# Intan_Interface.net
KiCad netlist of a schematic drawn in Altium Designer
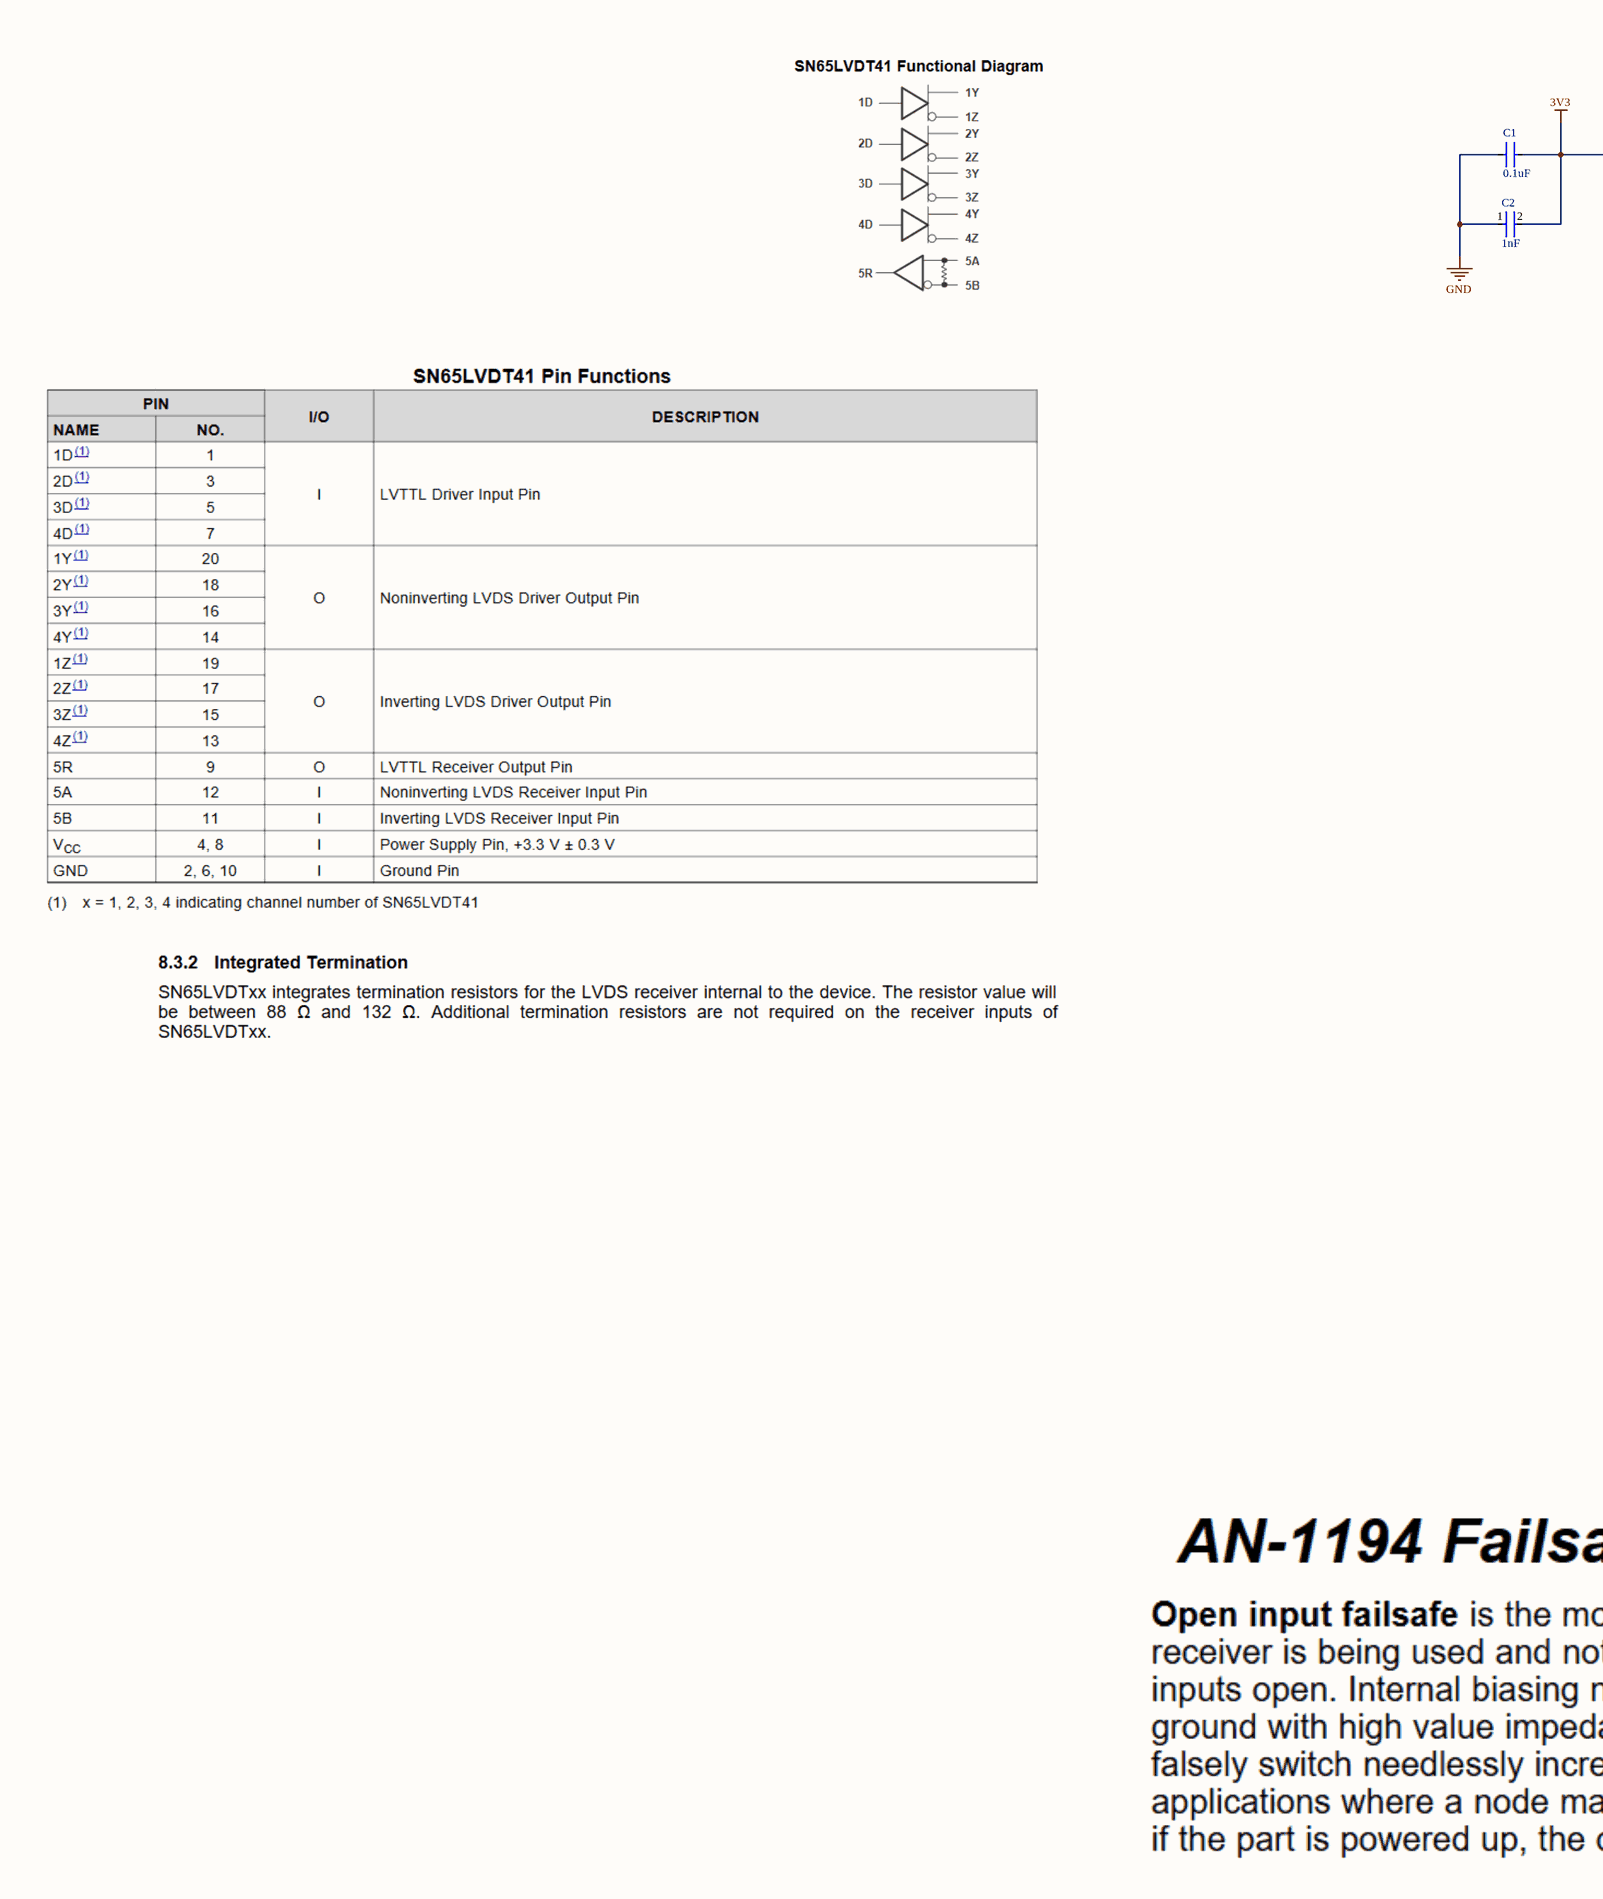
[diagram p0: Intan_Interface.SchDoc, left]
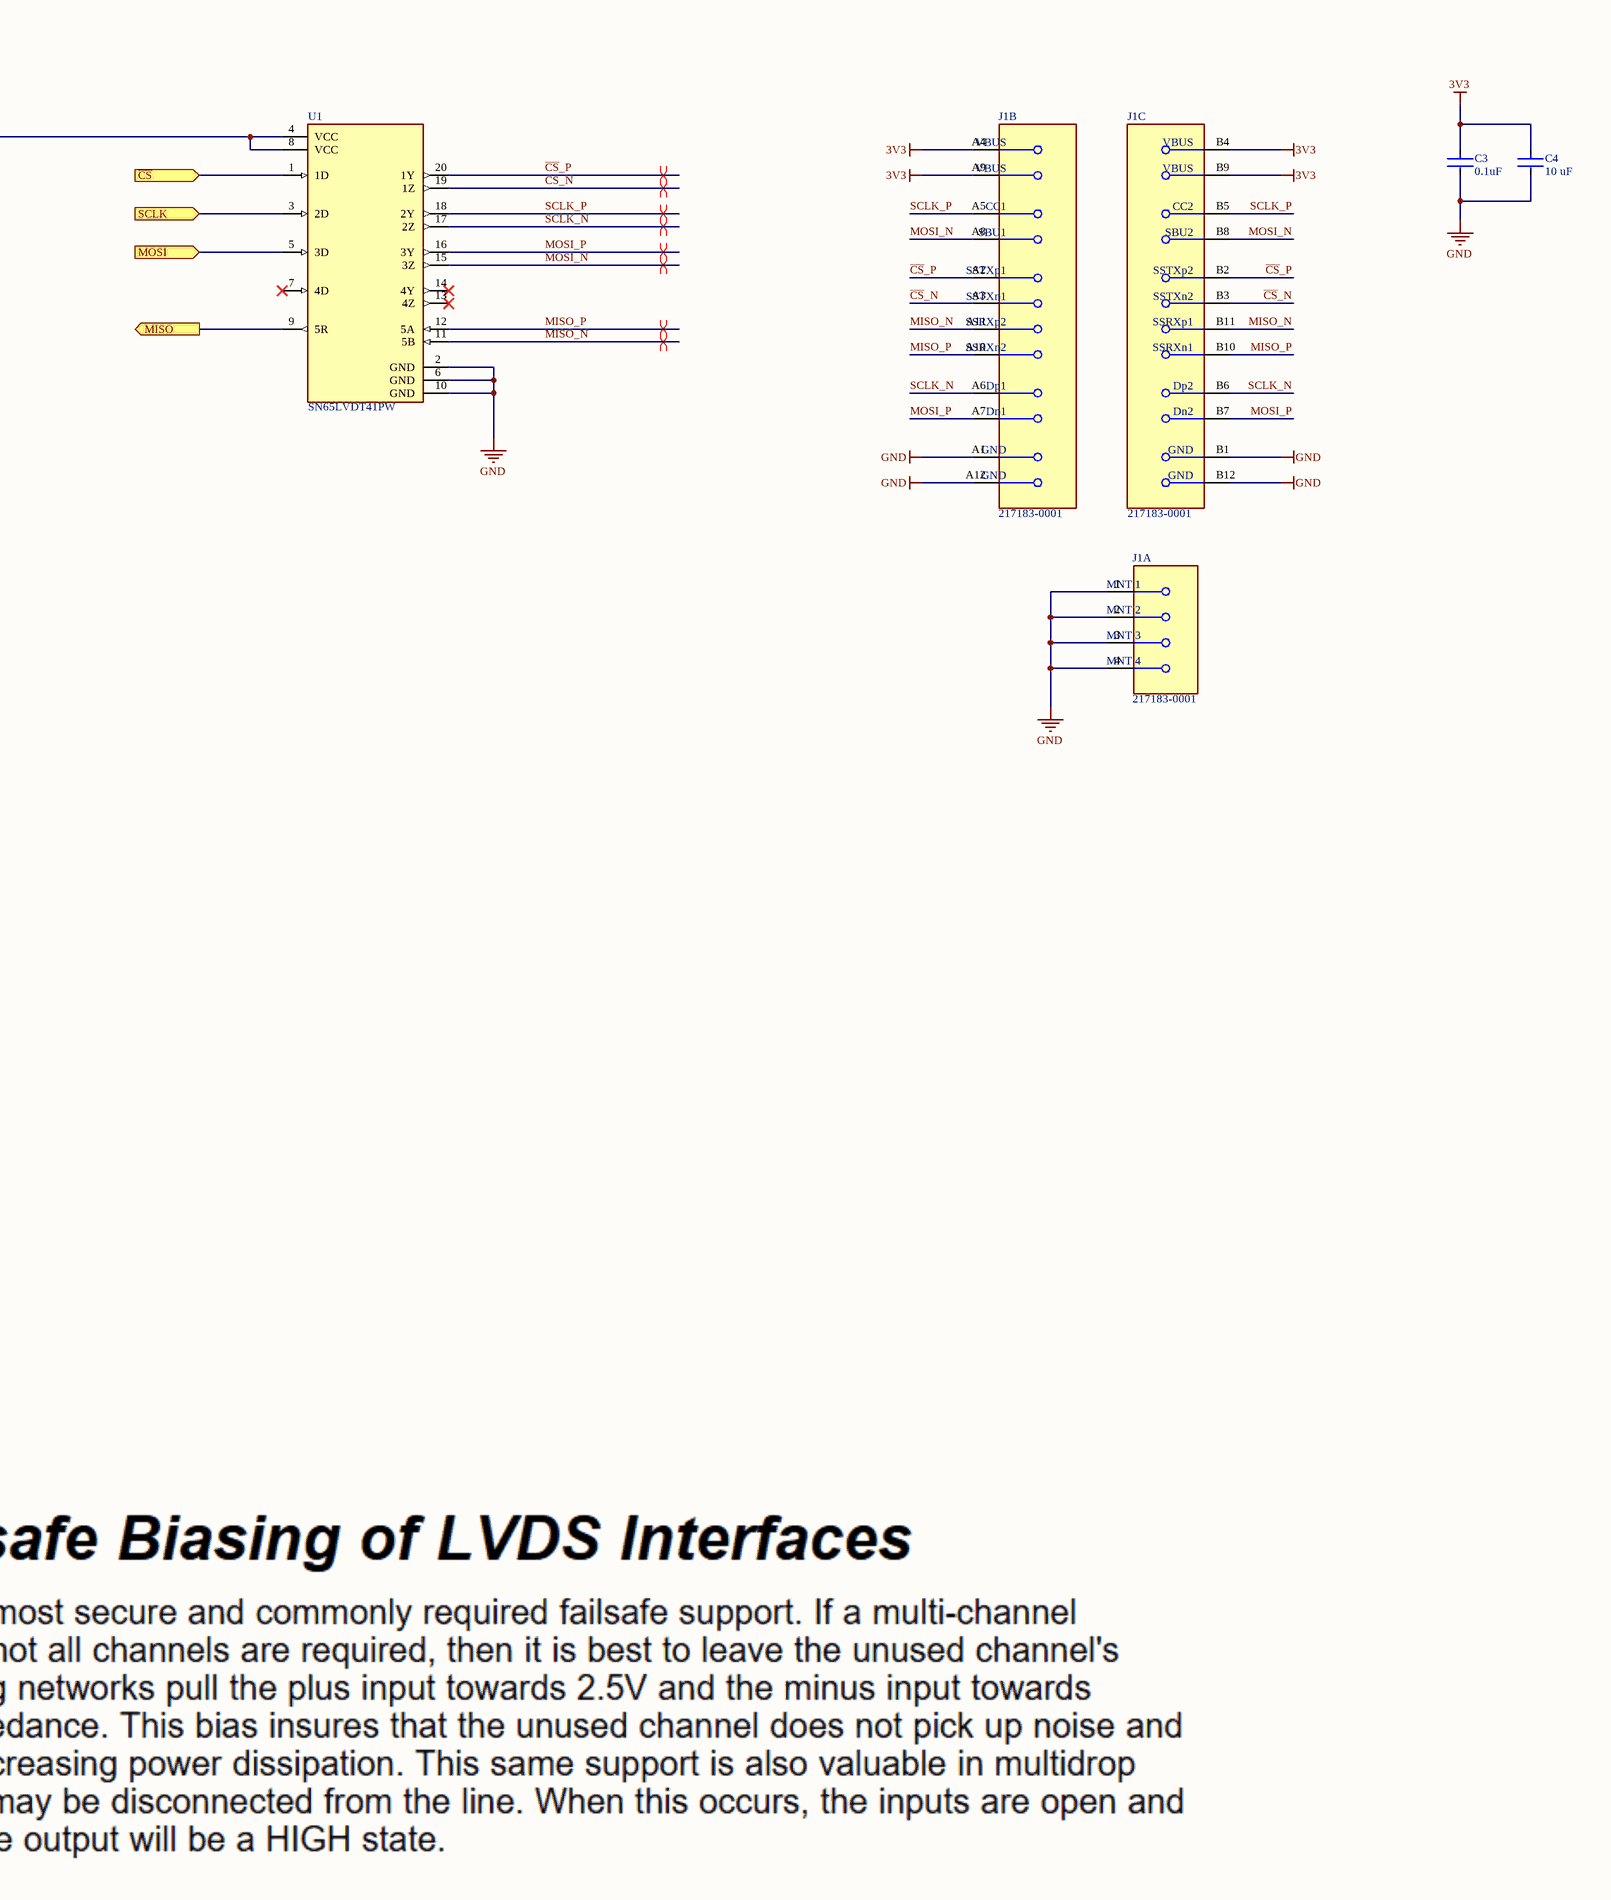
[diagram p1: Intan_Interface.SchDoc, right]

(export (version "E")
  (design (tool "Eeschema 10.0.6"))
  (components
    (comp (ref "C1")
      (value "0.1uF")
      (footprint "FP-CC0603-DA-IPC_B")
      (description "CAP CER 0.1UF 50V X7R 0603")
      (fields (field (name "MANUFACTURER") "YAGEO") (field (name "VOLTAGE") "50 V"))
      (libsource (lib "Capacitors") (part "CAP_0U10_0603"))
    )
    (comp (ref "C2")
      (value "1nF")
      (footprint "FP-CL10-IPC_A")
      (description "Cap Ceramic 1nF 50V X7R ±10% Pad SMD 0603 +125°C T/R")
      (fields (field (name "VOLTAGE") "50V") (field (name "TOLERANCE") "10%"))
      (libsource (lib "Capacitors") (part "CAP_1N00_0603"))
    )
    (comp (ref "C3")
      (value "0.1uF")
      (footprint "FP-CC0603-DA-IPC_B")
      (description "CAP CER 0.1UF 50V X7R 0603")
      (fields (field (name "MANUFACTURER") "YAGEO") (field (name "VOLTAGE") "50 V"))
      (libsource (lib "Capacitors") (part "CAP_0U10_0603"))
    )
    (comp (ref "C4")
      (value "10 uF")
      (footprint "FP-GRM188-0_2-IPC_C")
      (description "Chip Multilayer Ceramic Capacitors for General Purpose, 0603, 10uF, X7R, 15%, 10%, 10V")
      (libsource (lib "Capacitors") (part "CAP_10U0_0603"))
    )
    (comp (ref "J1")
      (value "217183-0001")
      (footprint "FP-217183-0001-MFG")
      (libsource (lib "") (part "CON_USBC_TH_SMT_1"))
    )
    (comp (ref "U1")
      (value "SN65LVDT41PW")
      (footprint "FP-PW0020A-IPC_C")
      (description "IC TRANSCEIVER HALF 4/1 20TSSOP")
      (libsource (lib "Altium Content Vault") (part "2e0bb46aa7ccf5e29cc7010412bd3a4"))
    )
  )
  (nets
    (net (code "2") (name "/MISO") (class "Default")
      (node (ref "U1") (pin "9") (pinfunction "5R_9") (pintype "output"))
    )
    (net (code "3") (name "/MISO_N") (class "Default")
      (node (ref "J1") (pin "A11") (pinfunction "SSRXp2_A11") (pintype "passive"))
      (node (ref "J1") (pin "B11") (pinfunction "SSRXp1_B11") (pintype "passive"))
      (node (ref "U1") (pin "11") (pinfunction "5B_11") (pintype "input"))
    )
    (net (code "4") (name "/MISO_P") (class "Default")
      (node (ref "J1") (pin "A10") (pinfunction "SSRXn2_A10") (pintype "passive"))
      (node (ref "J1") (pin "B10") (pinfunction "SSRXn1_B10") (pintype "passive"))
      (node (ref "U1") (pin "12") (pinfunction "5A_12") (pintype "input"))
    )
    (net (code "5") (name "/MOSI") (class "Default")
      (node (ref "U1") (pin "5") (pinfunction "3D_5") (pintype "input"))
    )
    (net (code "6") (name "/MOSI_N") (class "Default")
      (node (ref "J1") (pin "A8") (pinfunction "SBU1_A8") (pintype "passive"))
      (node (ref "J1") (pin "B8") (pinfunction "SBU2_B8") (pintype "passive"))
      (node (ref "U1") (pin "15") (pinfunction "3Z_15") (pintype "output"))
    )
    (net (code "7") (name "/MOSI_P") (class "Default")
      (node (ref "J1") (pin "A7") (pinfunction "Dn1_A7") (pintype "passive"))
      (node (ref "J1") (pin "B7") (pinfunction "Dn2_B7") (pintype "passive"))
      (node (ref "U1") (pin "16") (pinfunction "3Y_16") (pintype "output"))
    )
    (net (code "8") (name "/SCLK") (class "Default")
      (node (ref "U1") (pin "3") (pinfunction "2D_3") (pintype "input"))
    )
    (net (code "9") (name "/SCLK_N") (class "Default")
      (node (ref "J1") (pin "A6") (pinfunction "Dp1_A6") (pintype "passive"))
      (node (ref "J1") (pin "B6") (pinfunction "Dp2_B6") (pintype "passive"))
      (node (ref "U1") (pin "17") (pinfunction "2Z_17") (pintype "output"))
    )
    (net (code "10") (name "/SCLK_P") (class "Default")
      (node (ref "J1") (pin "A5") (pinfunction "CC1_A5") (pintype "passive"))
      (node (ref "J1") (pin "B5") (pinfunction "CC2_B5") (pintype "passive"))
      (node (ref "U1") (pin "18") (pinfunction "2Y_18") (pintype "output"))
    )
    (net (code "11") (name "/~{CS}") (class "Default")
      (node (ref "U1") (pin "1") (pinfunction "1D_1") (pintype "input"))
    )
    (net (code "12") (name "/~{CS}_N") (class "Default")
      (node (ref "J1") (pin "A3") (pinfunction "SSTXn1_A3") (pintype "passive"))
      (node (ref "J1") (pin "B3") (pinfunction "SSTXn2_B3") (pintype "passive"))
      (node (ref "U1") (pin "19") (pinfunction "1Z_19") (pintype "output"))
    )
    (net (code "13") (name "/~{CS}_P") (class "Default")
      (node (ref "J1") (pin "A2") (pinfunction "SSTXp1_A2") (pintype "passive"))
      (node (ref "J1") (pin "B2") (pinfunction "SSTXp2_B2") (pintype "passive"))
      (node (ref "U1") (pin "20") (pinfunction "1Y_20") (pintype "output"))
    )
    (net (code "14") (name "3V3") (class "Default")
      (node (ref "C1") (pin "1") (pinfunction "1_1") (pintype "passive"))
      (node (ref "C2") (pin "2") (pinfunction "2_2") (pintype "passive"))
      (node (ref "C3") (pin "1") (pinfunction "1_1") (pintype "passive"))
      (node (ref "C4") (pin "1") (pinfunction "1_1") (pintype "passive"))
      (node (ref "J1") (pin "A4") (pinfunction "VBUS_A4") (pintype "passive"))
      (node (ref "J1") (pin "A9") (pinfunction "VBUS_A9") (pintype "passive"))
      (node (ref "J1") (pin "B4") (pinfunction "VBUS_B4") (pintype "passive"))
      (node (ref "J1") (pin "B9") (pinfunction "VBUS_B9") (pintype "passive"))
      (node (ref "U1") (pin "4") (pinfunction "VCC_4") (pintype "power_in"))
      (node (ref "U1") (pin "8") (pinfunction "VCC_8") (pintype "power_in"))
    )
    (net (code "15") (name "GND") (class "Default")
      (node (ref "C1") (pin "2") (pinfunction "2_2") (pintype "passive"))
      (node (ref "C2") (pin "1") (pinfunction "1_1") (pintype "passive"))
      (node (ref "C3") (pin "2") (pinfunction "2_2") (pintype "passive"))
      (node (ref "C4") (pin "2") (pinfunction "2_2") (pintype "passive"))
      (node (ref "J1") (pin "1") (pinfunction "MNT_1_1") (pintype "passive"))
      (node (ref "J1") (pin "2") (pinfunction "MNT_2_2") (pintype "passive"))
      (node (ref "J1") (pin "3") (pinfunction "MNT_3_3") (pintype "passive"))
      (node (ref "J1") (pin "4") (pinfunction "MNT_4_4") (pintype "passive"))
      (node (ref "J1") (pin "A1") (pinfunction "GND_A1") (pintype "passive"))
      (node (ref "J1") (pin "A12") (pinfunction "GND_A12") (pintype "passive"))
      (node (ref "J1") (pin "B1") (pinfunction "GND_B1") (pintype "passive"))
      (node (ref "J1") (pin "B12") (pinfunction "GND_B12") (pintype "passive"))
      (node (ref "U1") (pin "10") (pinfunction "GND_10") (pintype "power_in"))
      (node (ref "U1") (pin "2") (pinfunction "GND_2") (pintype "power_in"))
      (node (ref "U1") (pin "6") (pinfunction "GND_6") (pintype "power_in"))
    )
    (net (code "16") (name "unconnected-(U1-4D-Pad7)") (class "Default")
      (node (ref "U1") (pin "7") (pinfunction "4D_7") (pintype "input+no_connect"))
    )
    (net (code "17") (name "unconnected-(U1-4Y-Pad14)") (class "Default")
      (node (ref "U1") (pin "14") (pinfunction "4Y_14") (pintype "output+no_connect"))
    )
    (net (code "18") (name "unconnected-(U1-4Z-Pad13)") (class "Default")
      (node (ref "U1") (pin "13") (pinfunction "4Z_13") (pintype "output+no_connect"))
    )
  )
)
